# PCB_One.net
KiCad netlist of a schematic drawn in EasyEDA
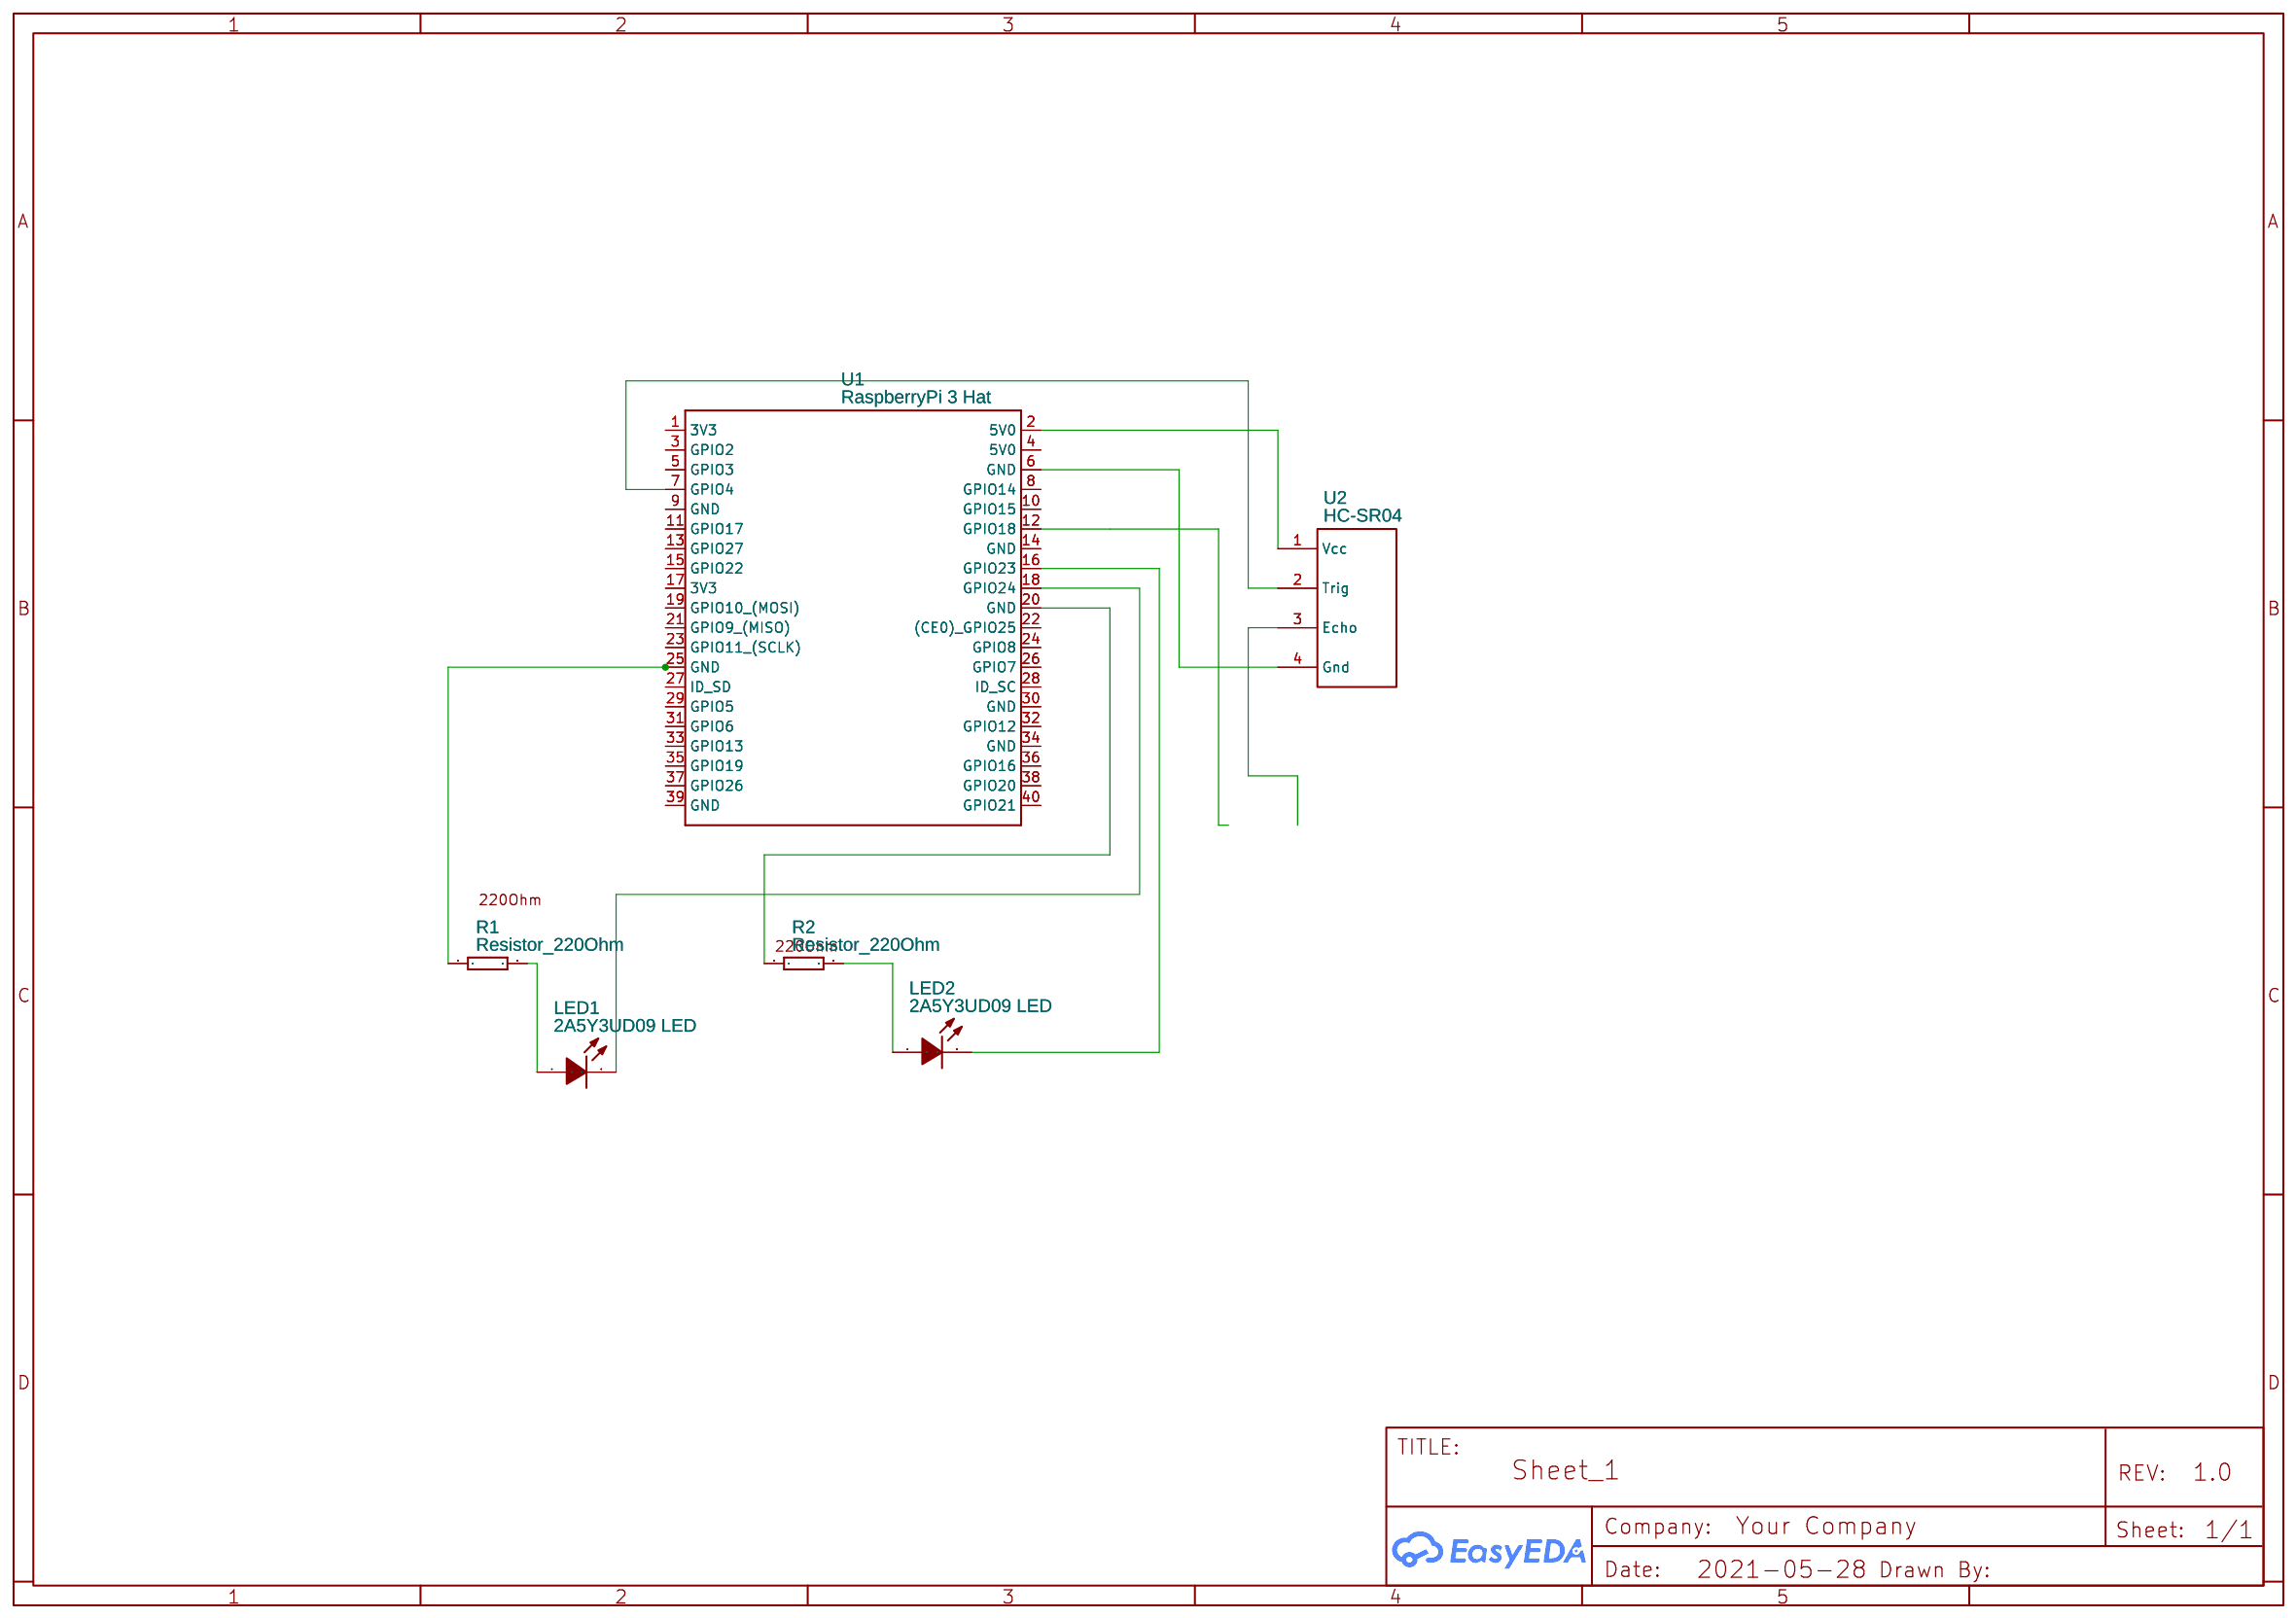
[diagram p0: schematic sheet]

(export (version "E")
  (design (tool "Eeschema 10.0.6"))
  (components
    (comp (ref "LED1")
      (value "2A5Y3UD09 LED")
      (fields (field (name "BOM_Supplier Part") "C3651"))
      (libsource (lib "") (part "2A5Y3UD09 LED"))
    )
    (comp (ref "LED2")
      (value "2A5Y3UD09 LED")
      (fields (field (name "BOM_Supplier Part") "C3651"))
      (libsource (lib "") (part "2A5Y3UD09 LED"))
    )
    (comp (ref "R1") (value "Resistor_220Ohm") (libsource (lib "") (part "Resistor_220Ohm")))
    (comp (ref "R2") (value "Resistor_220Ohm") (libsource (lib "") (part "Resistor_220Ohm_1")))
    (comp (ref "U1")
      (value "RaspberryPi 3 Hat")
      (fields (field (name "BOM_Manufacturer Part") "RaspberryPi 3"))
      (libsource (lib "") (part "RaspberryPi 3 Hat"))
    )
    (comp (ref "U2") (value "HC-SR04") (libsource (lib "") (part "HC-SR04")))
  )
  (nets
    (net (code "1") (name "Net-(LED1-+)") (class "Default")
      (node (ref "LED1") (pin "1") (pinfunction "+_1") (pintype "unspecified"))
      (node (ref "R1") (pin "2") (pinfunction "2_2") (pintype "unspecified"))
    )
    (net (code "2") (name "Net-(LED1--)") (class "Default")
      (node (ref "LED1") (pin "2") (pinfunction "-_2") (pintype "unspecified"))
      (node (ref "U1") (pin "18") (pinfunction "GPIO24_18") (pintype "unspecified"))
    )
    (net (code "3") (name "Net-(LED2-+)") (class "Default")
      (node (ref "LED2") (pin "1") (pinfunction "+_1") (pintype "unspecified"))
      (node (ref "R2") (pin "2") (pinfunction "2_2") (pintype "unspecified"))
    )
    (net (code "4") (name "Net-(LED2--)") (class "Default")
      (node (ref "LED2") (pin "2") (pinfunction "-_2") (pintype "unspecified"))
      (node (ref "U1") (pin "16") (pinfunction "GPIO23_16") (pintype "unspecified"))
    )
    (net (code "5") (name "Net-(R1-Pad1)") (class "Default")
      (node (ref "R1") (pin "1") (pinfunction "1_1") (pintype "unspecified"))
      (node (ref "U1") (pin "25") (pinfunction "GND_25") (pintype "unspecified"))
    )
    (net (code "6") (name "Net-(R2-Pad1)") (class "Default")
      (node (ref "R2") (pin "1") (pinfunction "1_1") (pintype "unspecified"))
      (node (ref "U1") (pin "20") (pinfunction "GND_20") (pintype "unspecified"))
    )
    (net (code "7") (name "Net-(U1-GPIO4)") (class "Default")
      (node (ref "U1") (pin "7") (pinfunction "GPIO4_7") (pintype "unspecified"))
      (node (ref "U2") (pin "2") (pinfunction "Trig_2") (pintype "unspecified"))
    )
    (net (code "8") (name "Net-(U2-Gnd)") (class "Default")
      (node (ref "U1") (pin "6") (pinfunction "GND_6") (pintype "unspecified"))
      (node (ref "U2") (pin "4") (pinfunction "Gnd_4") (pintype "unspecified"))
    )
    (net (code "9") (name "Net-(U2-Vcc)") (class "Default")
      (node (ref "U1") (pin "2") (pinfunction "5V0_2") (pintype "unspecified"))
      (node (ref "U2") (pin "1") (pinfunction "Vcc_1") (pintype "unspecified"))
    )
    (net (code "10") (name "unconnected-(U1-(CE0)_GPIO25-Pad22)") (class "Default")
      (node (ref "U1") (pin "22") (pinfunction "(CE0)_GPIO25_22") (pintype "unspecified"))
    )
    (net (code "11") (name "unconnected-(U1-3V3-Pad1)") (class "Default")
      (node (ref "U1") (pin "1") (pinfunction "3V3_1") (pintype "unspecified"))
    )
    (net (code "12") (name "unconnected-(U1-3V3-Pad17)") (class "Default")
      (node (ref "U1") (pin "17") (pinfunction "3V3_17") (pintype "unspecified"))
    )
    (net (code "13") (name "unconnected-(U1-5V0-Pad4)") (class "Default")
      (node (ref "U1") (pin "4") (pinfunction "5V0_4") (pintype "unspecified"))
    )
    (net (code "14") (name "unconnected-(U1-GND-Pad9)") (class "Default")
      (node (ref "U1") (pin "9") (pinfunction "GND_9") (pintype "unspecified"))
    )
    (net (code "15") (name "unconnected-(U1-GND-Pad14)") (class "Default")
      (node (ref "U1") (pin "14") (pinfunction "GND_14") (pintype "unspecified"))
    )
    (net (code "16") (name "unconnected-(U1-GND-Pad30)") (class "Default")
      (node (ref "U1") (pin "30") (pinfunction "GND_30") (pintype "unspecified"))
    )
    (net (code "17") (name "unconnected-(U1-GND-Pad34)") (class "Default")
      (node (ref "U1") (pin "34") (pinfunction "GND_34") (pintype "unspecified"))
    )
    (net (code "18") (name "unconnected-(U1-GND-Pad39)") (class "Default")
      (node (ref "U1") (pin "39") (pinfunction "GND_39") (pintype "unspecified"))
    )
    (net (code "19") (name "unconnected-(U1-GPIO2-Pad3)") (class "Default")
      (node (ref "U1") (pin "3") (pinfunction "GPIO2_3") (pintype "unspecified"))
    )
    (net (code "20") (name "unconnected-(U1-GPIO3-Pad5)") (class "Default")
      (node (ref "U1") (pin "5") (pinfunction "GPIO3_5") (pintype "unspecified"))
    )
    (net (code "21") (name "unconnected-(U1-GPIO5-Pad29)") (class "Default")
      (node (ref "U1") (pin "29") (pinfunction "GPIO5_29") (pintype "unspecified"))
    )
    (net (code "22") (name "unconnected-(U1-GPIO6-Pad31)") (class "Default")
      (node (ref "U1") (pin "31") (pinfunction "GPIO6_31") (pintype "unspecified"))
    )
    (net (code "23") (name "unconnected-(U1-GPIO7-Pad26)") (class "Default")
      (node (ref "U1") (pin "26") (pinfunction "GPIO7_26") (pintype "unspecified"))
    )
    (net (code "24") (name "unconnected-(U1-GPIO8-Pad24)") (class "Default")
      (node (ref "U1") (pin "24") (pinfunction "GPIO8_24") (pintype "unspecified"))
    )
    (net (code "25") (name "unconnected-(U1-GPIO9_(MISO)-Pad21)") (class "Default")
      (node (ref "U1") (pin "21") (pinfunction "GPIO9_(MISO)_21") (pintype "unspecified"))
    )
    (net (code "26") (name "unconnected-(U1-GPIO10_(MOSI)-Pad19)") (class "Default")
      (node (ref "U1") (pin "19") (pinfunction "GPIO10_(MOSI)_19") (pintype "unspecified"))
    )
    (net (code "27") (name "unconnected-(U1-GPIO11_(SCLK)-Pad23)") (class "Default")
      (node (ref "U1") (pin "23") (pinfunction "GPIO11_(SCLK)_23") (pintype "unspecified"))
    )
    (net (code "28") (name "unconnected-(U1-GPIO12-Pad32)") (class "Default")
      (node (ref "U1") (pin "32") (pinfunction "GPIO12_32") (pintype "unspecified"))
    )
    (net (code "29") (name "unconnected-(U1-GPIO13-Pad33)") (class "Default")
      (node (ref "U1") (pin "33") (pinfunction "GPIO13_33") (pintype "unspecified"))
    )
    (net (code "30") (name "unconnected-(U1-GPIO14-Pad8)") (class "Default")
      (node (ref "U1") (pin "8") (pinfunction "GPIO14_8") (pintype "unspecified"))
    )
    (net (code "31") (name "unconnected-(U1-GPIO15-Pad10)") (class "Default")
      (node (ref "U1") (pin "10") (pinfunction "GPIO15_10") (pintype "unspecified"))
    )
    (net (code "32") (name "unconnected-(U1-GPIO16-Pad36)") (class "Default")
      (node (ref "U1") (pin "36") (pinfunction "GPIO16_36") (pintype "unspecified"))
    )
    (net (code "33") (name "unconnected-(U1-GPIO17-Pad11)") (class "Default")
      (node (ref "U1") (pin "11") (pinfunction "GPIO17_11") (pintype "unspecified"))
    )
    (net (code "34") (name "unconnected-(U1-GPIO18-Pad12)") (class "Default")
      (node (ref "U1") (pin "12") (pinfunction "GPIO18_12") (pintype "unspecified"))
    )
    (net (code "35") (name "unconnected-(U1-GPIO19-Pad35)") (class "Default")
      (node (ref "U1") (pin "35") (pinfunction "GPIO19_35") (pintype "unspecified"))
    )
    (net (code "36") (name "unconnected-(U1-GPIO20-Pad38)") (class "Default")
      (node (ref "U1") (pin "38") (pinfunction "GPIO20_38") (pintype "unspecified"))
    )
    (net (code "37") (name "unconnected-(U1-GPIO21-Pad40)") (class "Default")
      (node (ref "U1") (pin "40") (pinfunction "GPIO21_40") (pintype "unspecified"))
    )
    (net (code "38") (name "unconnected-(U1-GPIO22-Pad15)") (class "Default")
      (node (ref "U1") (pin "15") (pinfunction "GPIO22_15") (pintype "unspecified"))
    )
    (net (code "39") (name "unconnected-(U1-GPIO26-Pad37)") (class "Default")
      (node (ref "U1") (pin "37") (pinfunction "GPIO26_37") (pintype "unspecified"))
    )
    (net (code "40") (name "unconnected-(U1-GPIO27-Pad13)") (class "Default")
      (node (ref "U1") (pin "13") (pinfunction "GPIO27_13") (pintype "unspecified"))
    )
    (net (code "41") (name "unconnected-(U1-ID_SC-Pad28)") (class "Default")
      (node (ref "U1") (pin "28") (pinfunction "ID_SC_28") (pintype "unspecified"))
    )
    (net (code "42") (name "unconnected-(U1-ID_SD-Pad27)") (class "Default")
      (node (ref "U1") (pin "27") (pinfunction "ID_SD_27") (pintype "unspecified"))
    )
    (net (code "43") (name "unconnected-(U2-Echo-Pad3)") (class "Default")
      (node (ref "U2") (pin "3") (pinfunction "Echo_3") (pintype "unspecified"))
    )
  )
)
